# EnguinoShieldSchematic.net
KiCad netlist of a schematic drawn in EAGLE
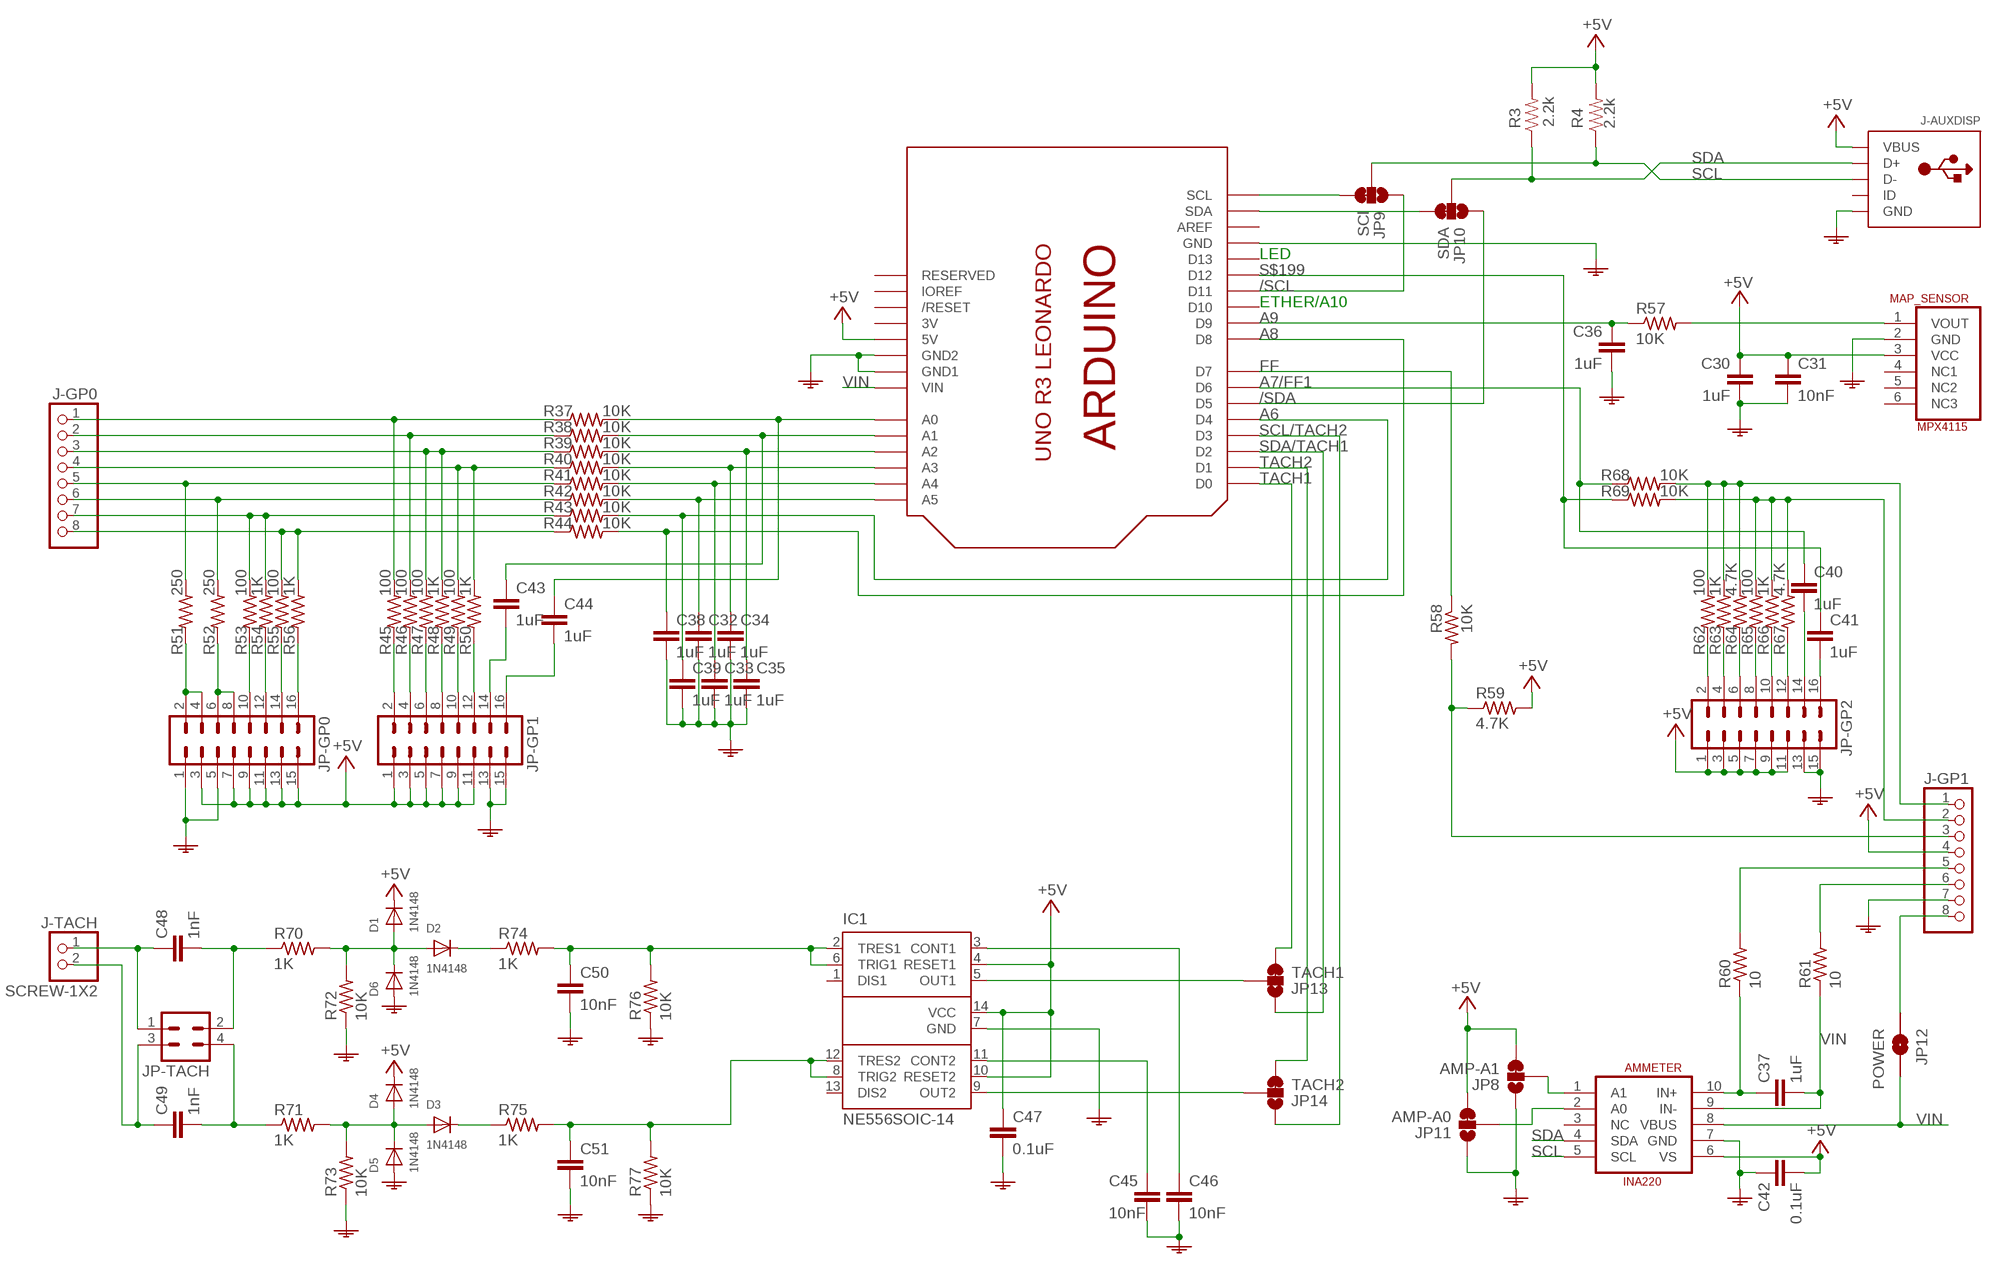
[diagram p0: schematic, sheet 1]
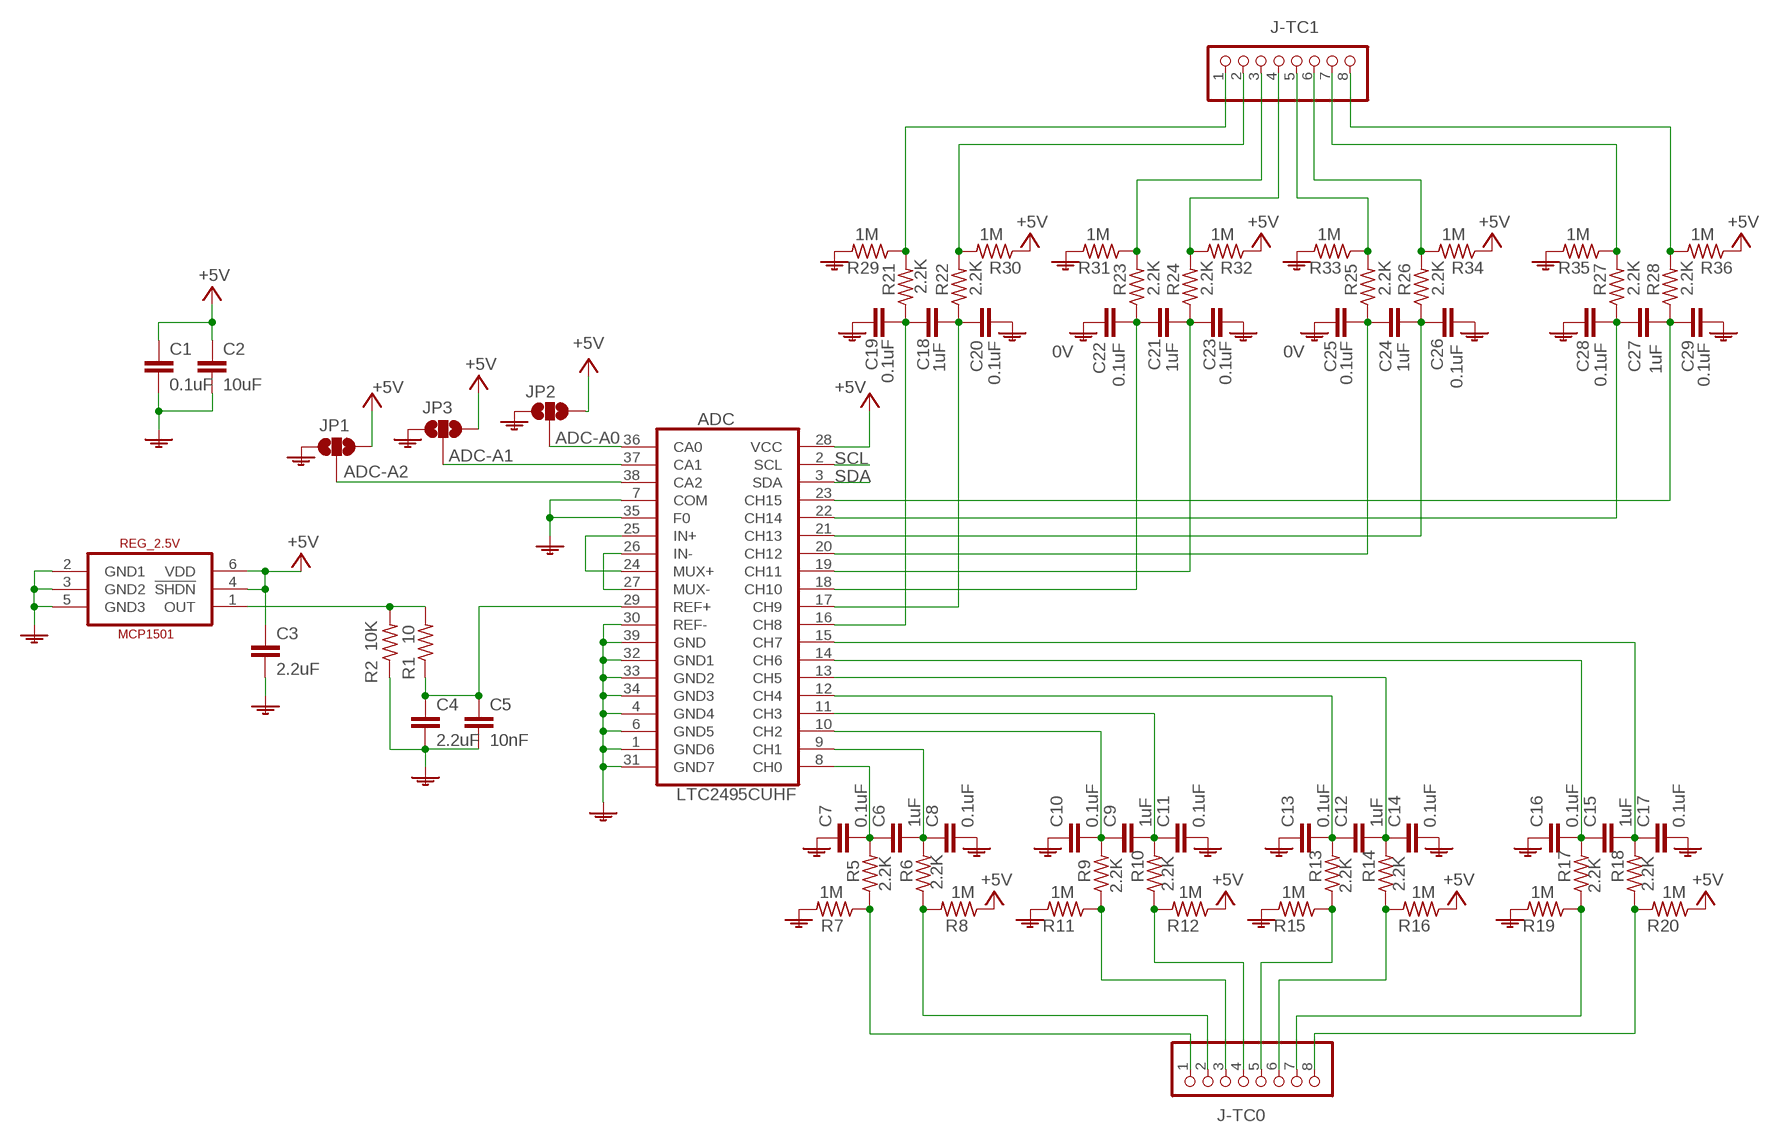
[diagram p1: schematic, sheet 2]

(export (version "E")
  (design (tool "Eeschema 10.0.6"))
  (components
    (comp (ref "AMMETER")
      (value "INA220")
      (footprint "eagle-import:VSSOP-10")
      (libsource (lib "eagle-import") (part "INA220"))
    )
    (comp (ref "C30")
      (value "1uF")
      (footprint "eagle-import:0603")
      (libsource (lib "eagle-import") (part "CAP-1UF10V"))
    )
    (comp (ref "C31")
      (value "10nF")
      (footprint "eagle-import:0603")
      (libsource (lib "eagle-import") (part "CAP-10NF"))
    )
    (comp (ref "C32")
      (value "1uF")
      (footprint "eagle-import:0603")
      (libsource (lib "eagle-import") (part "CAP-1UF10V"))
    )
    (comp (ref "C33")
      (value "1uF")
      (footprint "eagle-import:0603")
      (libsource (lib "eagle-import") (part "CAP-1UF10V"))
    )
    (comp (ref "C34")
      (value "1uF")
      (footprint "eagle-import:0603")
      (libsource (lib "eagle-import") (part "CAP-1UF10V"))
    )
    (comp (ref "C35")
      (value "1uF")
      (footprint "eagle-import:0603")
      (libsource (lib "eagle-import") (part "CAP-1UF10V"))
    )
    (comp (ref "C36")
      (value "1uF")
      (footprint "eagle-import:0603")
      (libsource (lib "eagle-import") (part "CAP-1UF10V"))
    )
    (comp (ref "C37")
      (value "1uF")
      (footprint "eagle-import:0603")
      (libsource (lib "eagle-import") (part "CAP-1UF10V"))
    )
    (comp (ref "C38")
      (value "1uF")
      (footprint "eagle-import:0603")
      (libsource (lib "eagle-import") (part "CAP-1UF10V"))
    )
    (comp (ref "C39")
      (value "1uF")
      (footprint "eagle-import:0603")
      (libsource (lib "eagle-import") (part "CAP-1UF10V"))
    )
    (comp (ref "C40")
      (value "1uF")
      (footprint "eagle-import:0603")
      (libsource (lib "eagle-import") (part "CAP-1UF10V"))
    )
    (comp (ref "C41")
      (value "1uF")
      (footprint "eagle-import:0603")
      (libsource (lib "eagle-import") (part "CAP-1UF10V"))
    )
    (comp (ref "C42")
      (value "0.1uF")
      (footprint "eagle-import:0603")
      (libsource (lib "eagle-import") (part "CAP-0.1UF10V"))
    )
    (comp (ref "C43")
      (value "1uF")
      (footprint "eagle-import:0603")
      (libsource (lib "eagle-import") (part "CAP-1UF10V"))
    )
    (comp (ref "C44")
      (value "1uF")
      (footprint "eagle-import:0603")
      (libsource (lib "eagle-import") (part "CAP-1UF10V"))
    )
    (comp (ref "C45")
      (value "10nF")
      (footprint "eagle-import:0603")
      (libsource (lib "eagle-import") (part "CAP-10NF"))
    )
    (comp (ref "C46")
      (value "10nF")
      (footprint "eagle-import:0603")
      (libsource (lib "eagle-import") (part "CAP-10NF"))
    )
    (comp (ref "C47")
      (value "0.1uF")
      (footprint "eagle-import:0603")
      (libsource (lib "eagle-import") (part "CAP-0.1UF10V"))
    )
    (comp (ref "C48")
      (value "1nF")
      (footprint "eagle-import:0603")
      (libsource (lib "eagle-import") (part "CAP-1NF"))
    )
    (comp (ref "C49")
      (value "1nF")
      (footprint "eagle-import:0603")
      (libsource (lib "eagle-import") (part "CAP-1NF"))
    )
    (comp (ref "C50")
      (value "10nF")
      (footprint "eagle-import:0603")
      (libsource (lib "eagle-import") (part "CAP-10NF"))
    )
    (comp (ref "C51")
      (value "10nF")
      (footprint "eagle-import:0603")
      (libsource (lib "eagle-import") (part "CAP-10NF"))
    )
    (comp (ref "D1")
      (value "1N4148")
      (footprint "eagle-import:SOD-123")
      (libsource (lib "eagle-import") (part "DIODESOD-123"))
    )
    (comp (ref "D2")
      (value "1N4148")
      (footprint "eagle-import:SOD-123")
      (libsource (lib "eagle-import") (part "DIODESOD-123"))
    )
    (comp (ref "D3")
      (value "1N4148")
      (footprint "eagle-import:SOD-123")
      (libsource (lib "eagle-import") (part "DIODESOD-123"))
    )
    (comp (ref "D4")
      (value "1N4148")
      (footprint "eagle-import:SOD-123")
      (libsource (lib "eagle-import") (part "DIODESOD-123"))
    )
    (comp (ref "D5")
      (value "1N4148")
      (footprint "eagle-import:SOD-123")
      (libsource (lib "eagle-import") (part "DIODESOD-123"))
    )
    (comp (ref "D6")
      (value "1N4148")
      (footprint "eagle-import:SOD-123")
      (libsource (lib "eagle-import") (part "DIODESOD-123"))
    )
    (comp (ref "IC1")
      (value "NE556SOIC-14")
      (footprint "eagle-import:SO14")
      (libsource (lib "eagle-import") (part "NE556SOIC-14"))
    )
    (comp (ref "J-AUXDISP")
      (value "USB-B-MICRO")
      (footprint "eagle-import:MICRO-USB-AMPHERNOL")
      (libsource (lib "eagle-import") (part "USB-B-MICRO"))
    )
    (comp (ref "J-GP0")
      (value "SCREW-1X8BIG")
      (footprint "eagle-import:1X08-BIG")
      (libsource (lib "eagle-import") (part "SCREW-1X8BIG"))
    )
    (comp (ref "J-GP1")
      (value "SCREW-1X8BIG")
      (footprint "eagle-import:1X08-BIG")
      (libsource (lib "eagle-import") (part "SCREW-1X8BIG"))
    )
    (comp (ref "J-TACH")
      (value "SCREW-1X2")
      (footprint "eagle-import:1X02-BIG")
      (libsource (lib "eagle-import") (part "SCREW-1X2"))
    )
    (comp (ref "JP-GP0")
      (value "MA08-2")
      (footprint "eagle-import:MA08-2")
      (libsource (lib "eagle-import") (part "MA08-2"))
    )
    (comp (ref "JP-GP1")
      (value "MA08-2")
      (footprint "eagle-import:MA08-2")
      (libsource (lib "eagle-import") (part "MA08-2"))
    )
    (comp (ref "JP-GP2")
      (value "MA08-2")
      (footprint "eagle-import:MA08-2")
      (libsource (lib "eagle-import") (part "MA08-2"))
    )
    (comp (ref "JP-TACH")
      (value "MA02-2")
      (footprint "eagle-import:MA02-2")
      (libsource (lib "eagle-import") (part "MA02-2"))
    )
    (comp (ref "JP8")
      (value "AMP-A1")
      (footprint "eagle-import:SMT-JUMPER_3_NC")
      (libsource (lib "eagle-import") (part "JUMPER-SMT_3-NC_NO-SILK"))
    )
    (comp (ref "JP9")
      (value "SCl")
      (footprint "eagle-import:SMT-JUMPER_3_NC")
      (libsource (lib "eagle-import") (part "JUMPER-SMT_3-NC_NO-SILK"))
    )
    (comp (ref "JP10")
      (value "SDA")
      (footprint "eagle-import:SMT-JUMPER_3_NC")
      (libsource (lib "eagle-import") (part "JUMPER-SMT_3-NC_NO-SILK"))
    )
    (comp (ref "JP11")
      (value "AMP-A0")
      (footprint "eagle-import:SMT-JUMPER_3_NC")
      (libsource (lib "eagle-import") (part "JUMPER-SMT_3-NC_NO-SILK"))
    )
    (comp (ref "JP12")
      (value "POWER")
      (footprint "eagle-import:SMT-JUMPER_2_NO")
      (libsource (lib "eagle-import") (part "JUMPER-SMT_2_NO_SILK"))
    )
    (comp (ref "JP13")
      (value "TACH1")
      (footprint "eagle-import:SMT-JUMPER_3_NC")
      (libsource (lib "eagle-import") (part "JUMPER-SMT_3-NC_NO-SILK"))
    )
    (comp (ref "JP14")
      (value "TACH2")
      (footprint "eagle-import:SMT-JUMPER_3_NC")
      (libsource (lib "eagle-import") (part "JUMPER-SMT_3-NC_NO-SILK"))
    )
    (comp (ref "MAP_SENSOR")
      (value "MPX4115")
      (footprint "eagle-import:MPX4115-AP")
      (libsource (lib "eagle-import") (part "MPX4115"))
    )
    (comp (ref "R3")
      (value "2.2k")
      (footprint "eagle-import:0603")
      (libsource (lib "eagle-import") (part "2.2KOHM-0603-1/10W-1%"))
    )
    (comp (ref "R4")
      (value "2.2k")
      (footprint "eagle-import:0603")
      (libsource (lib "eagle-import") (part "2.2KOHM-0603-1/10W-1%"))
    )
    (comp (ref "R37")
      (value "10K")
      (footprint "eagle-import:R0603")
      (libsource (lib "eagle-import") (part "R-US_R0603"))
    )
    (comp (ref "R38")
      (value "10K")
      (footprint "eagle-import:R0603")
      (libsource (lib "eagle-import") (part "R-US_R0603"))
    )
    (comp (ref "R39")
      (value "10K")
      (footprint "eagle-import:R0603")
      (libsource (lib "eagle-import") (part "R-US_R0603"))
    )
    (comp (ref "R40")
      (value "10K")
      (footprint "eagle-import:R0603")
      (libsource (lib "eagle-import") (part "R-US_R0603"))
    )
    (comp (ref "R41")
      (value "10K")
      (footprint "eagle-import:R0603")
      (libsource (lib "eagle-import") (part "R-US_R0603"))
    )
    (comp (ref "R42")
      (value "10K")
      (footprint "eagle-import:R0603")
      (libsource (lib "eagle-import") (part "R-US_R0603"))
    )
    (comp (ref "R43")
      (value "10K")
      (footprint "eagle-import:R0603")
      (libsource (lib "eagle-import") (part "R-US_R0603"))
    )
    (comp (ref "R44")
      (value "10K")
      (footprint "eagle-import:R0603")
      (libsource (lib "eagle-import") (part "R-US_R0603"))
    )
    (comp (ref "R45")
      (value "100")
      (footprint "eagle-import:R0603")
      (libsource (lib "eagle-import") (part "R-US_R0603"))
    )
    (comp (ref "R46")
      (value "100")
      (footprint "eagle-import:R0603")
      (libsource (lib "eagle-import") (part "R-US_R0603"))
    )
    (comp (ref "R47")
      (value "100")
      (footprint "eagle-import:R0603")
      (libsource (lib "eagle-import") (part "R-US_R0603"))
    )
    (comp (ref "R48")
      (value "1K")
      (footprint "eagle-import:R0603")
      (libsource (lib "eagle-import") (part "R-US_R0603"))
    )
    (comp (ref "R49")
      (value "100")
      (footprint "eagle-import:R0603")
      (libsource (lib "eagle-import") (part "R-US_R0603"))
    )
    (comp (ref "R50")
      (value "1K")
      (footprint "eagle-import:R0603")
      (libsource (lib "eagle-import") (part "R-US_R0603"))
    )
    (comp (ref "R51")
      (value "250")
      (footprint "eagle-import:R0603")
      (libsource (lib "eagle-import") (part "R-US_R0603"))
    )
    (comp (ref "R52")
      (value "250")
      (footprint "eagle-import:R0603")
      (libsource (lib "eagle-import") (part "R-US_R0603"))
    )
    (comp (ref "R53")
      (value "100")
      (footprint "eagle-import:R0603")
      (libsource (lib "eagle-import") (part "R-US_R0603"))
    )
    (comp (ref "R54")
      (value "1K")
      (footprint "eagle-import:R0603")
      (libsource (lib "eagle-import") (part "R-US_R0603"))
    )
    (comp (ref "R55")
      (value "100")
      (footprint "eagle-import:R0603")
      (libsource (lib "eagle-import") (part "R-US_R0603"))
    )
    (comp (ref "R56")
      (value "1K")
      (footprint "eagle-import:R0603")
      (libsource (lib "eagle-import") (part "R-US_R0603"))
    )
    (comp (ref "R57")
      (value "10K")
      (footprint "eagle-import:R0603")
      (libsource (lib "eagle-import") (part "R-US_R0603"))
    )
    (comp (ref "R58")
      (value "10K")
      (footprint "eagle-import:R0603")
      (libsource (lib "eagle-import") (part "R-US_R0603"))
    )
    (comp (ref "R59")
      (value "4.7K")
      (footprint "eagle-import:R0603")
      (libsource (lib "eagle-import") (part "R-US_R0603"))
    )
    (comp (ref "R60")
      (value "10")
      (footprint "eagle-import:R0603")
      (libsource (lib "eagle-import") (part "R-US_R0603"))
    )
    (comp (ref "R61")
      (value "10")
      (footprint "eagle-import:R0603")
      (libsource (lib "eagle-import") (part "R-US_R0603"))
    )
    (comp (ref "R62")
      (value "100")
      (footprint "eagle-import:R0603")
      (libsource (lib "eagle-import") (part "R-US_R0603"))
    )
    (comp (ref "R63")
      (value "1K")
      (footprint "eagle-import:R0603")
      (libsource (lib "eagle-import") (part "R-US_R0603"))
    )
    (comp (ref "R64")
      (value "4.7K")
      (footprint "eagle-import:R0603")
      (libsource (lib "eagle-import") (part "R-US_R0603"))
    )
    (comp (ref "R65")
      (value "100")
      (footprint "eagle-import:R0603")
      (libsource (lib "eagle-import") (part "R-US_R0603"))
    )
    (comp (ref "R66")
      (value "1K")
      (footprint "eagle-import:R0603")
      (libsource (lib "eagle-import") (part "R-US_R0603"))
    )
    (comp (ref "R67")
      (value "4.7K")
      (footprint "eagle-import:R0603")
      (libsource (lib "eagle-import") (part "R-US_R0603"))
    )
    (comp (ref "R68")
      (value "10K")
      (footprint "eagle-import:R0603")
      (libsource (lib "eagle-import") (part "R-US_R0603"))
    )
    (comp (ref "R69")
      (value "10K")
      (footprint "eagle-import:R0603")
      (libsource (lib "eagle-import") (part "R-US_R0603"))
    )
    (comp (ref "R70")
      (value "1K")
      (footprint "eagle-import:R0603")
      (libsource (lib "eagle-import") (part "R-US_R0603"))
    )
    (comp (ref "R71")
      (value "1K")
      (footprint "eagle-import:R0603")
      (libsource (lib "eagle-import") (part "R-US_R0603"))
    )
    (comp (ref "R72")
      (value "10K")
      (footprint "eagle-import:R0603")
      (libsource (lib "eagle-import") (part "R-US_R0603"))
    )
    (comp (ref "R73")
      (value "10K")
      (footprint "eagle-import:R0603")
      (libsource (lib "eagle-import") (part "R-US_R0603"))
    )
    (comp (ref "R74")
      (value "1K")
      (footprint "eagle-import:R0603")
      (libsource (lib "eagle-import") (part "R-US_R0603"))
    )
    (comp (ref "R75")
      (value "1K")
      (footprint "eagle-import:R0603")
      (libsource (lib "eagle-import") (part "R-US_R0603"))
    )
    (comp (ref "R76")
      (value "10K")
      (footprint "eagle-import:R0603")
      (libsource (lib "eagle-import") (part "R-US_R0603"))
    )
    (comp (ref "R77")
      (value "10K")
      (footprint "eagle-import:R0603")
      (libsource (lib "eagle-import") (part "R-US_R0603"))
    )
    (comp (ref "U1")
      (value "ARDUINOR3LEO-DIMENSION")
      (footprint "eagle-import:ARDUINOR3")
      (libsource (lib "eagle-import") (part "ARDUINOR3LEO-DIMENSION"))
    )
    (comp (ref "ADC")
      (value "LTC2495CUHF")
      (footprint "eagle-import:QFN-38")
      (libsource (lib "eagle-import") (part "LTC2495CUHF"))
    )
    (comp (ref "C1")
      (value "0.1uF")
      (footprint "eagle-import:0603")
      (libsource (lib "eagle-import") (part "CAP-0.1UF10V"))
    )
    (comp (ref "C2")
      (value "10uF")
      (footprint "eagle-import:0603")
      (libsource (lib "eagle-import") (part "CAP-10UF10V"))
    )
    (comp (ref "C3")
      (value "2.2uF")
      (footprint "eagle-import:0603")
      (libsource (lib "eagle-import") (part "CAP-2.2UF10V"))
    )
    (comp (ref "C4")
      (value "2.2uF")
      (footprint "eagle-import:0603")
      (libsource (lib "eagle-import") (part "CAP-2.2UF10V"))
    )
    (comp (ref "C5")
      (value "10nF")
      (footprint "eagle-import:0603")
      (libsource (lib "eagle-import") (part "CAP-10NF"))
    )
    (comp (ref "C6")
      (value "1uF")
      (footprint "eagle-import:0603")
      (libsource (lib "eagle-import") (part "CAP-1UF10V"))
    )
    (comp (ref "C7")
      (value "0.1uF")
      (footprint "eagle-import:0603")
      (libsource (lib "eagle-import") (part "CAP-0.1UF10V"))
    )
    (comp (ref "C8")
      (value "0.1uF")
      (footprint "eagle-import:0603")
      (libsource (lib "eagle-import") (part "CAP-0.1UF10V"))
    )
    (comp (ref "C9")
      (value "1uF")
      (footprint "eagle-import:0603")
      (libsource (lib "eagle-import") (part "CAP-1UF10V"))
    )
    (comp (ref "C10")
      (value "0.1uF")
      (footprint "eagle-import:0603")
      (libsource (lib "eagle-import") (part "CAP-0.1UF10V"))
    )
    (comp (ref "C11")
      (value "0.1uF")
      (footprint "eagle-import:0603")
      (libsource (lib "eagle-import") (part "CAP-0.1UF10V"))
    )
    (comp (ref "C12")
      (value "1uF")
      (footprint "eagle-import:0603")
      (libsource (lib "eagle-import") (part "CAP-1UF10V"))
    )
    (comp (ref "C13")
      (value "0.1uF")
      (footprint "eagle-import:0603")
      (libsource (lib "eagle-import") (part "CAP-0.1UF10V"))
    )
    (comp (ref "C14")
      (value "0.1uF")
      (footprint "eagle-import:0603")
      (libsource (lib "eagle-import") (part "CAP-0.1UF10V"))
    )
    (comp (ref "C15")
      (value "1uF")
      (footprint "eagle-import:0603")
      (libsource (lib "eagle-import") (part "CAP-1UF10V"))
    )
    (comp (ref "C16")
      (value "0.1uF")
      (footprint "eagle-import:0603")
      (libsource (lib "eagle-import") (part "CAP-0.1UF10V"))
    )
    (comp (ref "C17")
      (value "0.1uF")
      (footprint "eagle-import:0603")
      (libsource (lib "eagle-import") (part "CAP-0.1UF10V"))
    )
    (comp (ref "C18")
      (value "1uF")
      (footprint "eagle-import:0603")
      (libsource (lib "eagle-import") (part "CAP-1UF10V"))
    )
    (comp (ref "C19")
      (value "0.1uF")
      (footprint "eagle-import:0603")
      (libsource (lib "eagle-import") (part "CAP-0.1UF10V"))
    )
    (comp (ref "C20")
      (value "0.1uF")
      (footprint "eagle-import:0603")
      (libsource (lib "eagle-import") (part "CAP-0.1UF10V"))
    )
    (comp (ref "C21")
      (value "1uF")
      (footprint "eagle-import:0603")
      (libsource (lib "eagle-import") (part "CAP-1UF10V"))
    )
    (comp (ref "C22")
      (value "0.1uF")
      (footprint "eagle-import:0603")
      (libsource (lib "eagle-import") (part "CAP-0.1UF10V"))
    )
    (comp (ref "C23")
      (value "0.1uF")
      (footprint "eagle-import:0603")
      (libsource (lib "eagle-import") (part "CAP-0.1UF10V"))
    )
    (comp (ref "C24")
      (value "1uF")
      (footprint "eagle-import:0603")
      (libsource (lib "eagle-import") (part "CAP-1UF10V"))
    )
    (comp (ref "C25")
      (value "0.1uF")
      (footprint "eagle-import:0603")
      (libsource (lib "eagle-import") (part "CAP-0.1UF10V"))
    )
    (comp (ref "C26")
      (value "0.1uF")
      (footprint "eagle-import:0603")
      (libsource (lib "eagle-import") (part "CAP-0.1UF10V"))
    )
    (comp (ref "C27")
      (value "1uF")
      (footprint "eagle-import:0603")
      (libsource (lib "eagle-import") (part "CAP-1UF10V"))
    )
    (comp (ref "C28")
      (value "0.1uF")
      (footprint "eagle-import:0603")
      (libsource (lib "eagle-import") (part "CAP-0.1UF10V"))
    )
    (comp (ref "C29")
      (value "0.1uF")
      (footprint "eagle-import:0603")
      (libsource (lib "eagle-import") (part "CAP-0.1UF10V"))
    )
    (comp (ref "J-TC0")
      (value "SCREW-1X8BIG")
      (footprint "eagle-import:1X08-BIG")
      (libsource (lib "eagle-import") (part "SCREW-1X8BIG"))
    )
    (comp (ref "J-TC1")
      (value "SCREW-1X8BIG")
      (footprint "eagle-import:1X08-BIG")
      (libsource (lib "eagle-import") (part "SCREW-1X8BIG"))
    )
    (comp (ref "JP1")
      (value "ADC-A2")
      (footprint "eagle-import:SMT-JUMPER_3_NO")
      (libsource (lib "eagle-import") (part "JUMPER-SMT_3_NO_NO-SILK"))
    )
    (comp (ref "JP2")
      (value "ADC-A0")
      (footprint "eagle-import:SMT-JUMPER_3_NO")
      (libsource (lib "eagle-import") (part "JUMPER-SMT_3_NO_NO-SILK"))
    )
    (comp (ref "JP3")
      (value "ADC-A1")
      (footprint "eagle-import:SMT-JUMPER_3_NO")
      (libsource (lib "eagle-import") (part "JUMPER-SMT_3_NO_NO-SILK"))
    )
    (comp (ref "R1")
      (value "10")
      (footprint "eagle-import:R0603")
      (libsource (lib "eagle-import") (part "R-US_R0603"))
    )
    (comp (ref "R2")
      (value "10K")
      (footprint "eagle-import:R0603")
      (libsource (lib "eagle-import") (part "R-US_R0603"))
    )
    (comp (ref "R5")
      (value "2.2K")
      (footprint "eagle-import:R0603")
      (libsource (lib "eagle-import") (part "R-US_R0603"))
    )
    (comp (ref "R6")
      (value "2.2K")
      (footprint "eagle-import:R0603")
      (libsource (lib "eagle-import") (part "R-US_R0603"))
    )
    (comp (ref "R7")
      (value "1M")
      (footprint "eagle-import:R0603")
      (libsource (lib "eagle-import") (part "R-US_R0603"))
    )
    (comp (ref "R8")
      (value "1M")
      (footprint "eagle-import:R0603")
      (libsource (lib "eagle-import") (part "R-US_R0603"))
    )
    (comp (ref "R9")
      (value "2.2K")
      (footprint "eagle-import:R0603")
      (libsource (lib "eagle-import") (part "R-US_R0603"))
    )
    (comp (ref "R10")
      (value "2.2K")
      (footprint "eagle-import:R0603")
      (libsource (lib "eagle-import") (part "R-US_R0603"))
    )
    (comp (ref "R11")
      (value "1M")
      (footprint "eagle-import:R0603")
      (libsource (lib "eagle-import") (part "R-US_R0603"))
    )
    (comp (ref "R12")
      (value "1M")
      (footprint "eagle-import:R0603")
      (libsource (lib "eagle-import") (part "R-US_R0603"))
    )
    (comp (ref "R13")
      (value "2.2K")
      (footprint "eagle-import:R0603")
      (libsource (lib "eagle-import") (part "R-US_R0603"))
    )
    (comp (ref "R14")
      (value "2.2K")
      (footprint "eagle-import:R0603")
      (libsource (lib "eagle-import") (part "R-US_R0603"))
    )
    (comp (ref "R15")
      (value "1M")
      (footprint "eagle-import:R0603")
      (libsource (lib "eagle-import") (part "R-US_R0603"))
    )
    (comp (ref "R16")
      (value "1M")
      (footprint "eagle-import:R0603")
      (libsource (lib "eagle-import") (part "R-US_R0603"))
    )
    (comp (ref "R17")
      (value "2.2K")
      (footprint "eagle-import:R0603")
      (libsource (lib "eagle-import") (part "R-US_R0603"))
    )
    (comp (ref "R18")
      (value "2.2K")
      (footprint "eagle-import:R0603")
      (libsource (lib "eagle-import") (part "R-US_R0603"))
    )
    (comp (ref "R19")
      (value "1M")
      (footprint "eagle-import:R0603")
      (libsource (lib "eagle-import") (part "R-US_R0603"))
    )
    (comp (ref "R20")
      (value "1M")
      (footprint "eagle-import:R0603")
      (libsource (lib "eagle-import") (part "R-US_R0603"))
    )
    (comp (ref "R21")
      (value "2.2K")
      (footprint "eagle-import:R0603")
      (libsource (lib "eagle-import") (part "R-US_R0603"))
    )
    (comp (ref "R22")
      (value "2.2K")
      (footprint "eagle-import:R0603")
      (libsource (lib "eagle-import") (part "R-US_R0603"))
    )
    (comp (ref "R23")
      (value "2.2K")
      (footprint "eagle-import:R0603")
      (libsource (lib "eagle-import") (part "R-US_R0603"))
    )
    (comp (ref "R24")
      (value "2.2K")
      (footprint "eagle-import:R0603")
      (libsource (lib "eagle-import") (part "R-US_R0603"))
    )
    (comp (ref "R25")
      (value "2.2K")
      (footprint "eagle-import:R0603")
      (libsource (lib "eagle-import") (part "R-US_R0603"))
    )
    (comp (ref "R26")
      (value "2.2K")
      (footprint "eagle-import:R0603")
      (libsource (lib "eagle-import") (part "R-US_R0603"))
    )
    (comp (ref "R27")
      (value "2.2K")
      (footprint "eagle-import:R0603")
      (libsource (lib "eagle-import") (part "R-US_R0603"))
    )
    (comp (ref "R28")
      (value "2.2K")
      (footprint "eagle-import:R0603")
      (libsource (lib "eagle-import") (part "R-US_R0603"))
    )
    (comp (ref "R29")
      (value "1M")
      (footprint "eagle-import:R0603")
      (libsource (lib "eagle-import") (part "R-US_R0603"))
    )
    (comp (ref "R30")
      (value "1M")
      (footprint "eagle-import:R0603")
      (libsource (lib "eagle-import") (part "R-US_R0603"))
    )
    (comp (ref "R31")
      (value "1M")
      (footprint "eagle-import:R0603")
      (libsource (lib "eagle-import") (part "R-US_R0603"))
    )
    (comp (ref "R32")
      (value "1M")
      (footprint "eagle-import:R0603")
      (libsource (lib "eagle-import") (part "R-US_R0603"))
    )
    (comp (ref "R33")
      (value "1M")
      (footprint "eagle-import:R0603")
      (libsource (lib "eagle-import") (part "R-US_R0603"))
    )
    (comp (ref "R34")
      (value "1M")
      (footprint "eagle-import:R0603")
      (libsource (lib "eagle-import") (part "R-US_R0603"))
    )
    (comp (ref "R35")
      (value "1M")
      (footprint "eagle-import:R0603")
      (libsource (lib "eagle-import") (part "R-US_R0603"))
    )
    (comp (ref "R36")
      (value "1M")
      (footprint "eagle-import:R0603")
      (libsource (lib "eagle-import") (part "R-US_R0603"))
    )
    (comp (ref "REG_2.5V")
      (value "MCP1501")
      (footprint "eagle-import:SOT23-6")
      (libsource (lib "eagle-import") (part "MCP1501"))
    )
  )
  (nets
    (net (code "1") (name "+5V") (class "Default")
      (node (ref "ADC") (pin "28") (pinfunction "VCC_28") (pintype "power_in"))
      (node (ref "AMMETER") (pin "6") (pinfunction "VS_6") (pintype "power_in"))
      (node (ref "C1") (pin "1") (pinfunction "1_1") (pintype "passive"))
      (node (ref "C2") (pin "1") (pinfunction "1_1") (pintype "passive"))
      (node (ref "C3") (pin "1") (pinfunction "1_1") (pintype "passive"))
      (node (ref "C30") (pin "1") (pinfunction "1_1") (pintype "passive"))
      (node (ref "C31") (pin "1") (pinfunction "1_1") (pintype "passive"))
      (node (ref "C42") (pin "2") (pinfunction "2_2") (pintype "passive"))
      (node (ref "C47") (pin "1") (pinfunction "1_1") (pintype "passive"))
      (node (ref "D1") (pin "C") (pinfunction "C_C") (pintype "passive"))
      (node (ref "D4") (pin "C") (pinfunction "C_C") (pintype "passive"))
      (node (ref "IC1") (pin "10") (pinfunction "RESET2_10") (pintype "input"))
      (node (ref "IC1") (pin "14") (pinfunction "VCC_14") (pintype "power_in"))
      (node (ref "IC1") (pin "4") (pinfunction "RESET1_4") (pintype "input"))
      (node (ref "J-AUXDISP") (pin "P$1") (pinfunction "VBUS_P$1") (pintype "power_in"))
      (node (ref "J-GP1") (pin "4") (pinfunction "4_4") (pintype "passive"))
      (node (ref "JP-GP0") (pin "11") (pinfunction "11_11") (pintype "passive"))
      (node (ref "JP-GP0") (pin "13") (pinfunction "13_13") (pintype "passive"))
      (node (ref "JP-GP0") (pin "15") (pinfunction "15_15") (pintype "passive"))
      (node (ref "JP-GP0") (pin "3") (pinfunction "3_3") (pintype "passive"))
      (node (ref "JP-GP0") (pin "7") (pinfunction "7_7") (pintype "passive"))
      (node (ref "JP-GP0") (pin "9") (pinfunction "9_9") (pintype "passive"))
      (node (ref "JP-GP1") (pin "1") (pinfunction "1_1") (pintype "passive"))
      (node (ref "JP-GP1") (pin "11") (pinfunction "11_11") (pintype "passive"))
      (node (ref "JP-GP1") (pin "3") (pinfunction "3_3") (pintype "passive"))
      (node (ref "JP-GP1") (pin "5") (pinfunction "5_5") (pintype "passive"))
      (node (ref "JP-GP1") (pin "7") (pinfunction "7_7") (pintype "passive"))
      (node (ref "JP-GP1") (pin "9") (pinfunction "9_9") (pintype "passive"))
      (node (ref "JP-GP2") (pin "1") (pinfunction "1_1") (pintype "passive"))
      (node (ref "JP-GP2") (pin "11") (pinfunction "11_11") (pintype "passive"))
      (node (ref "JP-GP2") (pin "3") (pinfunction "3_3") (pintype "passive"))
      (node (ref "JP-GP2") (pin "5") (pinfunction "5_5") (pintype "passive"))
      (node (ref "JP-GP2") (pin "7") (pinfunction "7_7") (pintype "passive"))
      (node (ref "JP-GP2") (pin "9") (pinfunction "9_9") (pintype "passive"))
      (node (ref "JP1") (pin "3") (pinfunction "3_3") (pintype "passive"))
      (node (ref "JP11") (pin "3") (pinfunction "3_3") (pintype "passive"))
      (node (ref "JP2") (pin "3") (pinfunction "3_3") (pintype "passive"))
      (node (ref "JP3") (pin "3") (pinfunction "3_3") (pintype "passive"))
      (node (ref "JP8") (pin "3") (pinfunction "3_3") (pintype "passive"))
      (node (ref "MAP_SENSOR") (pin "3") (pinfunction "VCC_3") (pintype "power_in"))
      (node (ref "R12") (pin "1") (pinfunction "1_1") (pintype "passive"))
      (node (ref "R16") (pin "1") (pinfunction "1_1") (pintype "passive"))
      (node (ref "R20") (pin "1") (pinfunction "1_1") (pintype "passive"))
      (node (ref "R3") (pin "2") (pinfunction "2_2") (pintype "passive"))
      (node (ref "R30") (pin "1") (pinfunction "1_1") (pintype "passive"))
      (node (ref "R32") (pin "1") (pinfunction "1_1") (pintype "passive"))
      (node (ref "R34") (pin "1") (pinfunction "1_1") (pintype "passive"))
      (node (ref "R36") (pin "1") (pinfunction "1_1") (pintype "passive"))
      (node (ref "R4") (pin "2") (pinfunction "2_2") (pintype "passive"))
      (node (ref "R59") (pin "2") (pinfunction "2_2") (pintype "passive"))
      (node (ref "R8") (pin "1") (pinfunction "1_1") (pintype "passive"))
      (node (ref "REG_2.5V") (pin "4") (pinfunction "~{SHDN}_4") (pintype "bidirectional"))
      (node (ref "REG_2.5V") (pin "6") (pinfunction "VDD_6") (pintype "power_in"))
      (node (ref "U1") (pin "5V") (pinfunction "5V_5V") (pintype "power_in"))
    )
    (net (code "2") (name "0V") (class "Default")
      (node (ref "ADC") (pin "1") (pinfunction "GND6_1") (pintype "power_in"))
      (node (ref "ADC") (pin "30") (pinfunction "REF-_30") (pintype "bidirectional"))
      (node (ref "ADC") (pin "31") (pinfunction "GND7_31") (pintype "power_in"))
      (node (ref "ADC") (pin "32") (pinfunction "GND1_32") (pintype "power_in"))
      (node (ref "ADC") (pin "33") (pinfunction "GND2_33") (pintype "power_in"))
      (node (ref "ADC") (pin "34") (pinfunction "GND3_34") (pintype "power_in"))
      (node (ref "ADC") (pin "35") (pinfunction "F0_35") (pintype "bidirectional"))
      (node (ref "ADC") (pin "39") (pinfunction "GND_39") (pintype "power_in"))
      (node (ref "ADC") (pin "4") (pinfunction "GND4_4") (pintype "power_in"))
      (node (ref "ADC") (pin "6") (pinfunction "GND5_6") (pintype "power_in"))
      (node (ref "ADC") (pin "7") (pinfunction "COM_7") (pintype "bidirectional"))
      (node (ref "AMMETER") (pin "7") (pinfunction "GND_7") (pintype "power_in"))
      (node (ref "C1") (pin "2") (pinfunction "2_2") (pintype "passive"))
      (node (ref "C10") (pin "1") (pinfunction "1_1") (pintype "passive"))
      (node (ref "C11") (pin "2") (pinfunction "2_2") (pintype "passive"))
      (node (ref "C13") (pin "1") (pinfunction "1_1") (pintype "passive"))
      (node (ref "C14") (pin "2") (pinfunction "2_2") (pintype "passive"))
      (node (ref "C16") (pin "1") (pinfunction "1_1") (pintype "passive"))
      (node (ref "C17") (pin "2") (pinfunction "2_2") (pintype "passive"))
      (node (ref "C19") (pin "1") (pinfunction "1_1") (pintype "passive"))
      (node (ref "C2") (pin "2") (pinfunction "2_2") (pintype "passive"))
      (node (ref "C20") (pin "2") (pinfunction "2_2") (pintype "passive"))
      (node (ref "C22") (pin "1") (pinfunction "1_1") (pintype "passive"))
      (node (ref "C23") (pin "2") (pinfunction "2_2") (pintype "passive"))
      (node (ref "C25") (pin "1") (pinfunction "1_1") (pintype "passive"))
      (node (ref "C26") (pin "2") (pinfunction "2_2") (pintype "passive"))
      (node (ref "C28") (pin "1") (pinfunction "1_1") (pintype "passive"))
      (node (ref "C29") (pin "2") (pinfunction "2_2") (pintype "passive"))
      (node (ref "C3") (pin "2") (pinfunction "2_2") (pintype "passive"))
      (node (ref "C30") (pin "2") (pinfunction "2_2") (pintype "passive"))
      (node (ref "C31") (pin "2") (pinfunction "2_2") (pintype "passive"))
      (node (ref "C32") (pin "2") (pinfunction "2_2") (pintype "passive"))
      (node (ref "C33") (pin "2") (pinfunction "2_2") (pintype "passive"))
      (node (ref "C34") (pin "2") (pinfunction "2_2") (pintype "passive"))
      (node (ref "C35") (pin "2") (pinfunction "2_2") (pintype "passive"))
      (node (ref "C36") (pin "2") (pinfunction "2_2") (pintype "passive"))
      (node (ref "C38") (pin "2") (pinfunction "2_2") (pintype "passive"))
      (node (ref "C39") (pin "2") (pinfunction "2_2") (pintype "passive"))
      (node (ref "C4") (pin "2") (pinfunction "2_2") (pintype "passive"))
      (node (ref "C42") (pin "1") (pinfunction "1_1") (pintype "passive"))
      (node (ref "C45") (pin "2") (pinfunction "2_2") (pintype "passive"))
      (node (ref "C46") (pin "2") (pinfunction "2_2") (pintype "passive"))
      (node (ref "C47") (pin "2") (pinfunction "2_2") (pintype "passive"))
      (node (ref "C5") (pin "2") (pinfunction "2_2") (pintype "passive"))
      (node (ref "C50") (pin "2") (pinfunction "2_2") (pintype "passive"))
      (node (ref "C51") (pin "2") (pinfunction "2_2") (pintype "passive"))
      (node (ref "C7") (pin "1") (pinfunction "1_1") (pintype "passive"))
      (node (ref "C8") (pin "2") (pinfunction "2_2") (pintype "passive"))
      (node (ref "D5") (pin "A") (pinfunction "A_A") (pintype "passive"))
      (node (ref "D6") (pin "A") (pinfunction "A_A") (pintype "passive"))
      (node (ref "IC1") (pin "7") (pinfunction "GND_7") (pintype "power_in"))
      (node (ref "J-AUXDISP") (pin "P$5") (pinfunction "GND_P$5") (pintype "power_in"))
      (node (ref "J-GP1") (pin "7") (pinfunction "7_7") (pintype "passive"))
      (node (ref "JP-GP0") (pin "1") (pinfunction "1_1") (pintype "passive"))
      (node (ref "JP-GP0") (pin "5") (pinfunction "5_5") (pintype "passive"))
      (node (ref "JP-GP1") (pin "13") (pinfunction "13_13") (pintype "passive"))
      (node (ref "JP-GP1") (pin "15") (pinfunction "15_15") (pintype "passive"))
      (node (ref "JP-GP2") (pin "13") (pinfunction "13_13") (pintype "passive"))
      (node (ref "JP-GP2") (pin "15") (pinfunction "15_15") (pintype "passive"))
      (node (ref "JP1") (pin "1") (pinfunction "1_1") (pintype "passive"))
      (node (ref "JP11") (pin "1") (pinfunction "1_1") (pintype "passive"))
      (node (ref "JP2") (pin "1") (pinfunction "1_1") (pintype "passive"))
      (node (ref "JP3") (pin "1") (pinfunction "1_1") (pintype "passive"))
      (node (ref "JP8") (pin "1") (pinfunction "1_1") (pintype "passive"))
      (node (ref "MAP_SENSOR") (pin "2") (pinfunction "GND_2") (pintype "power_in"))
      (node (ref "R11") (pin "2") (pinfunction "2_2") (pintype "passive"))
      (node (ref "R15") (pin "2") (pinfunction "2_2") (pintype "passive"))
      (node (ref "R19") (pin "2") (pinfunction "2_2") (pintype "passive"))
      (node (ref "R2") (pin "1") (pinfunction "1_1") (pintype "passive"))
      (node (ref "R29") (pin "2") (pinfunction "2_2") (pintype "passive"))
      (node (ref "R31") (pin "2") (pinfunction "2_2") (pintype "passive"))
      (node (ref "R33") (pin "2") (pinfunction "2_2") (pintype "passive"))
      (node (ref "R35") (pin "2") (pinfunction "2_2") (pintype "passive"))
      (node (ref "R7") (pin "2") (pinfunction "2_2") (pintype "passive"))
      (node (ref "R72") (pin "1") (pinfunction "1_1") (pintype "passive"))
      (node (ref "R73") (pin "1") (pinfunction "1_1") (pintype "passive"))
      (node (ref "R76") (pin "1") (pinfunction "1_1") (pintype "passive"))
      (node (ref "R77") (pin "1") (pinfunction "1_1") (pintype "passive"))
      (node (ref "REG_2.5V") (pin "2") (pinfunction "GND1_2") (pintype "power_in"))
      (node (ref "REG_2.5V") (pin "3") (pinfunction "GND2_3") (pintype "power_in"))
      (node (ref "REG_2.5V") (pin "5") (pinfunction "GND3_5") (pintype "power_in"))
      (node (ref "U1") (pin "GND") (pinfunction "GND_GND") (pintype "power_in"))
      (node (ref "U1") (pin "GND1") (pinfunction "GND1_GND1") (pintype "power_in"))
      (node (ref "U1") (pin "GND2") (pinfunction "GND2_GND2") (pintype "power_in"))
    )
    (net (code "3") (name "3V") (class "Default")
      (node (ref "U1") (pin "3V") (pinfunction "3V_3V") (pintype "power_in"))
    )
    (net (code "4") (name "A6") (class "Default")
      (node (ref "C39") (pin "1") (pinfunction "1_1") (pintype "passive"))
      (node (ref "R43") (pin "2") (pinfunction "2_2") (pintype "passive"))
      (node (ref "U1") (pin "D4") (pinfunction "D4_D4") (pintype "bidirectional"))
    )
    (net (code "5") (name "A7{slash}FF1") (class "Default")
      (node (ref "C40") (pin "1") (pinfunction "1_1") (pintype "passive"))
      (node (ref "R68") (pin "1") (pinfunction "1_1") (pintype "passive"))
      (node (ref "U1") (pin "D6") (pinfunction "D6_D6") (pintype "bidirectional"))
    )
    (net (code "6") (name "A8") (class "Default")
      (node (ref "C38") (pin "1") (pinfunction "1_1") (pintype "passive"))
      (node (ref "R44") (pin "2") (pinfunction "2_2") (pintype "passive"))
      (node (ref "U1") (pin "D8") (pinfunction "D8_D8") (pintype "bidirectional"))
    )
    (net (code "7") (name "A9") (class "Default")
      (node (ref "C36") (pin "1") (pinfunction "1_1") (pintype "passive"))
      (node (ref "R57") (pin "1") (pinfunction "1_1") (pintype "passive"))
      (node (ref "U1") (pin "D9") (pinfunction "D9_D9") (pintype "bidirectional"))
    )
    (net (code "8") (name "FF") (class "Default")
      (node (ref "R58") (pin "1") (pinfunction "1_1") (pintype "passive"))
      (node (ref "U1") (pin "D7") (pinfunction "D7_D7") (pintype "bidirectional"))
    )
    (net (code "9") (name "Net-(ADC-CA0)") (class "Default")
      (node (ref "ADC") (pin "36") (pinfunction "CA0_36") (pintype "bidirectional"))
      (node (ref "JP2") (pin "2") (pinfunction "2_2") (pintype "passive"))
    )
    (net (code "10") (name "Net-(ADC-CA1)") (class "Default")
      (node (ref "ADC") (pin "37") (pinfunction "CA1_37") (pintype "bidirectional"))
      (node (ref "JP3") (pin "2") (pinfunction "2_2") (pintype "passive"))
    )
    (net (code "11") (name "Net-(ADC-CA2)") (class "Default")
      (node (ref "ADC") (pin "38") (pinfunction "CA2_38") (pintype "bidirectional"))
      (node (ref "JP1") (pin "2") (pinfunction "2_2") (pintype "passive"))
    )
    (net (code "12") (name "Net-(ADC-CH0)") (class "Default")
      (node (ref "ADC") (pin "8") (pinfunction "CH0_8") (pintype "bidirectional"))
      (node (ref "C6") (pin "1") (pinfunction "1_1") (pintype "passive"))
      (node (ref "C7") (pin "2") (pinfunction "2_2") (pintype "passive"))
      (node (ref "R5") (pin "2") (pinfunction "2_2") (pintype "passive"))
    )
    (net (code "13") (name "Net-(ADC-CH1)") (class "Default")
      (node (ref "ADC") (pin "9") (pinfunction "CH1_9") (pintype "bidirectional"))
      (node (ref "C6") (pin "2") (pinfunction "2_2") (pintype "passive"))
      (node (ref "C8") (pin "1") (pinfunction "1_1") (pintype "passive"))
      (node (ref "R6") (pin "2") (pinfunction "2_2") (pintype "passive"))
    )
    (net (code "14") (name "Net-(ADC-CH2)") (class "Default")
      (node (ref "ADC") (pin "10") (pinfunction "CH2_10") (pintype "bidirectional"))
      (node (ref "C10") (pin "2") (pinfunction "2_2") (pintype "passive"))
      (node (ref "C9") (pin "1") (pinfunction "1_1") (pintype "passive"))
      (node (ref "R9") (pin "2") (pinfunction "2_2") (pintype "passive"))
    )
    (net (code "15") (name "Net-(ADC-CH3)") (class "Default")
      (node (ref "ADC") (pin "11") (pinfunction "CH3_11") (pintype "bidirectional"))
      (node (ref "C11") (pin "1") (pinfunction "1_1") (pintype "passive"))
      (node (ref "C9") (pin "2") (pinfunction "2_2") (pintype "passive"))
      (node (ref "R10") (pin "2") (pinfunction "2_2") (pintype "passive"))
    )
    (net (code "16") (name "Net-(ADC-CH4)") (class "Default")
      (node (ref "ADC") (pin "12") (pinfunction "CH4_12") (pintype "bidirectional"))
      (node (ref "C12") (pin "1") (pinfunction "1_1") (pintype "passive"))
      (node (ref "C13") (pin "2") (pinfunction "2_2") (pintype "passive"))
      (node (ref "R13") (pin "2") (pinfunction "2_2") (pintype "passive"))
    )
    (net (code "17") (name "Net-(ADC-CH5)") (class "Default")
      (node (ref "ADC") (pin "13") (pinfunction "CH5_13") (pintype "bidirectional"))
      (node (ref "C12") (pin "2") (pinfunction "2_2") (pintype "passive"))
      (node (ref "C14") (pin "1") (pinfunction "1_1") (pintype "passive"))
      (node (ref "R14") (pin "2") (pinfunction "2_2") (pintype "passive"))
    )
    (net (code "18") (name "Net-(ADC-CH6)") (class "Default")
      (node (ref "ADC") (pin "14") (pinfunction "CH6_14") (pintype "bidirectional"))
      (node (ref "C15") (pin "1") (pinfunction "1_1") (pintype "passive"))
      (node (ref "C16") (pin "2") (pinfunction "2_2") (pintype "passive"))
      (node (ref "R17") (pin "2") (pinfunction "2_2") (pintype "passive"))
    )
    (net (code "19") (name "Net-(ADC-CH7)") (class "Default")
      (node (ref "ADC") (pin "15") (pinfunction "CH7_15") (pintype "bidirectional"))
      (node (ref "C15") (pin "2") (pinfunction "2_2") (pintype "passive"))
      (node (ref "C17") (pin "1") (pinfunction "1_1") (pintype "passive"))
      (node (ref "R18") (pin "2") (pinfunction "2_2") (pintype "passive"))
    )
    (net (code "20") (name "Net-(ADC-CH8)") (class "Default")
      (node (ref "ADC") (pin "16") (pinfunction "CH8_16") (pintype "bidirectional"))
      (node (ref "C18") (pin "1") (pinfunction "1_1") (pintype "passive"))
      (node (ref "C19") (pin "2") (pinfunction "2_2") (pintype "passive"))
      (node (ref "R21") (pin "1") (pinfunction "1_1") (pintype "passive"))
    )
    (net (code "21") (name "Net-(ADC-CH9)") (class "Default")
      (node (ref "ADC") (pin "17") (pinfunction "CH9_17") (pintype "bidirectional"))
      (node (ref "C18") (pin "2") (pinfunction "2_2") (pintype "passive"))
      (node (ref "C20") (pin "1") (pinfunction "1_1") (pintype "passive"))
      (node (ref "R22") (pin "1") (pinfunction "1_1") (pintype "passive"))
    )
    (net (code "22") (name "Net-(ADC-CH10)") (class "Default")
      (node (ref "ADC") (pin "18") (pinfunction "CH10_18") (pintype "bidirectional"))
      (node (ref "C21") (pin "1") (pinfunction "1_1") (pintype "passive"))
      (node (ref "C22") (pin "2") (pinfunction "2_2") (pintype "passive"))
      (node (ref "R23") (pin "1") (pinfunction "1_1") (pintype "passive"))
    )
    (net (code "23") (name "Net-(ADC-CH11)") (class "Default")
      (node (ref "ADC") (pin "19") (pinfunction "CH11_19") (pintype "bidirectional"))
      (node (ref "C21") (pin "2") (pinfunction "2_2") (pintype "passive"))
      (node (ref "C23") (pin "1") (pinfunction "1_1") (pintype "passive"))
      (node (ref "R24") (pin "1") (pinfunction "1_1") (pintype "passive"))
    )
    (net (code "24") (name "Net-(ADC-CH12)") (class "Default")
      (node (ref "ADC") (pin "20") (pinfunction "CH12_20") (pintype "bidirectional"))
      (node (ref "C24") (pin "1") (pinfunction "1_1") (pintype "passive"))
      (node (ref "C25") (pin "2") (pinfunction "2_2") (pintype "passive"))
      (node (ref "R25") (pin "1") (pinfunction "1_1") (pintype "passive"))
    )
    (net (code "25") (name "Net-(ADC-CH13)") (class "Default")
      (node (ref "ADC") (pin "21") (pinfunction "CH13_21") (pintype "bidirectional"))
      (node (ref "C24") (pin "2") (pinfunction "2_2") (pintype "passive"))
      (node (ref "C26") (pin "1") (pinfunction "1_1") (pintype "passive"))
      (node (ref "R26") (pin "1") (pinfunction "1_1") (pintype "passive"))
    )
    (net (code "26") (name "Net-(ADC-CH14)") (class "Default")
      (node (ref "ADC") (pin "22") (pinfunction "CH14_22") (pintype "bidirectional"))
      (node (ref "C27") (pin "1") (pinfunction "1_1") (pintype "passive"))
      (node (ref "C28") (pin "2") (pinfunction "2_2") (pintype "passive"))
      (node (ref "R27") (pin "1") (pinfunction "1_1") (pintype "passive"))
    )
    (net (code "27") (name "Net-(ADC-CH15)") (class "Default")
      (node (ref "ADC") (pin "23") (pinfunction "CH15_23") (pintype "bidirectional"))
      (node (ref "C27") (pin "2") (pinfunction "2_2") (pintype "passive"))
      (node (ref "C29") (pin "1") (pinfunction "1_1") (pintype "passive"))
      (node (ref "R28") (pin "1") (pinfunction "1_1") (pintype "passive"))
    )
    (net (code "28") (name "Net-(ADC-IN+)") (class "Default")
      (node (ref "ADC") (pin "24") (pinfunction "MUX+_24") (pintype "bidirectional"))
      (node (ref "ADC") (pin "25") (pinfunction "IN+_25") (pintype "bidirectional"))
    )
    (net (code "29") (name "Net-(ADC-IN-)") (class "Default")
      (node (ref "ADC") (pin "26") (pinfunction "IN-_26") (pintype "bidirectional"))
      (node (ref "ADC") (pin "27") (pinfunction "MUX-_27") (pintype "bidirectional"))
    )
    (net (code "30") (name "Net-(ADC-REF+)") (class "Default")
      (node (ref "ADC") (pin "29") (pinfunction "REF+_29") (pintype "bidirectional"))
      (node (ref "C4") (pin "1") (pinfunction "1_1") (pintype "passive"))
      (node (ref "C5") (pin "1") (pinfunction "1_1") (pintype "passive"))
      (node (ref "R1") (pin "1") (pinfunction "1_1") (pintype "passive"))
    )
    (net (code "31") (name "Net-(AMMETER-A0)") (class "Default")
      (node (ref "AMMETER") (pin "2") (pinfunction "A0_2") (pintype "bidirectional"))
      (node (ref "JP11") (pin "2") (pinfunction "2_2") (pintype "passive"))
    )
    (net (code "32") (name "Net-(AMMETER-A1)") (class "Default")
      (node (ref "AMMETER") (pin "1") (pinfunction "A1_1") (pintype "bidirectional"))
      (node (ref "JP8") (pin "2") (pinfunction "2_2") (pintype "passive"))
    )
    (net (code "33") (name "Net-(AMMETER-IN+)") (class "Default")
      (node (ref "AMMETER") (pin "10") (pinfunction "IN+_10") (pintype "bidirectional"))
      (node (ref "C37") (pin "1") (pinfunction "1_1") (pintype "passive"))
      (node (ref "R60") (pin "1") (pinfunction "1_1") (pintype "passive"))
    )
    (net (code "34") (name "Net-(AMMETER-IN-)") (class "Default")
      (node (ref "AMMETER") (pin "9") (pinfunction "IN-_9") (pintype "bidirectional"))
      (node (ref "C37") (pin "2") (pinfunction "2_2") (pintype "passive"))
      (node (ref "R61") (pin "1") (pinfunction "1_1") (pintype "passive"))
    )
    (net (code "35") (name "Net-(C32-Pad1)") (class "Default")
      (node (ref "C32") (pin "1") (pinfunction "1_1") (pintype "passive"))
      (node (ref "R42") (pin "2") (pinfunction "2_2") (pintype "passive"))
      (node (ref "U1") (pin "A5") (pinfunction "A5_A5") (pintype "bidirectional"))
    )
    (net (code "36") (name "Net-(C33-Pad1)") (class "Default")
      (node (ref "C33") (pin "1") (pinfunction "1_1") (pintype "passive"))
      (node (ref "R41") (pin "2") (pinfunction "2_2") (pintype "passive"))
      (node (ref "U1") (pin "A4") (pinfunction "A4_A4") (pintype "bidirectional"))
    )
    (net (code "37") (name "Net-(C34-Pad1)") (class "Default")
      (node (ref "C34") (pin "1") (pinfunction "1_1") (pintype "passive"))
      (node (ref "R40") (pin "2") (pinfunction "2_2") (pintype "passive"))
      (node (ref "U1") (pin "A3") (pinfunction "A3_A3") (pintype "bidirectional"))
    )
    (net (code "38") (name "Net-(C35-Pad1)") (class "Default")
      (node (ref "C35") (pin "1") (pinfunction "1_1") (pintype "passive"))
      (node (ref "R39") (pin "2") (pinfunction "2_2") (pintype "passive"))
      (node (ref "U1") (pin "A2") (pinfunction "A2_A2") (pintype "bidirectional"))
    )
    (net (code "39") (name "Net-(C40-Pad2)") (class "Default")
      (node (ref "C40") (pin "2") (pinfunction "2_2") (pintype "passive"))
      (node (ref "JP-GP2") (pin "14") (pinfunction "14_14") (pintype "passive"))
    )
    (net (code "40") (name "Net-(C41-Pad2)") (class "Default")
      (node (ref "C41") (pin "2") (pinfunction "2_2") (pintype "passive"))
      (node (ref "JP-GP2") (pin "16") (pinfunction "16_16") (pintype "passive"))
    )
    (net (code "41") (name "Net-(C43-Pad1)") (class "Default")
      (node (ref "C43") (pin "1") (pinfunction "1_1") (pintype "passive"))
      (node (ref "R38") (pin "2") (pinfunction "2_2") (pintype "passive"))
      (node (ref "U1") (pin "A1") (pinfunction "A1_A1") (pintype "bidirectional"))
    )
    (net (code "42") (name "Net-(C43-Pad2)") (class "Default")
      (node (ref "C43") (pin "2") (pinfunction "2_2") (pintype "passive"))
      (node (ref "JP-GP1") (pin "14") (pinfunction "14_14") (pintype "passive"))
    )
    (net (code "43") (name "Net-(C44-Pad1)") (class "Default")
      (node (ref "C44") (pin "1") (pinfunction "1_1") (pintype "passive"))
      (node (ref "R37") (pin "2") (pinfunction "2_2") (pintype "passive"))
      (node (ref "U1") (pin "A0") (pinfunction "A0_A0") (pintype "bidirectional"))
    )
    (net (code "44") (name "Net-(C44-Pad2)") (class "Default")
      (node (ref "C44") (pin "2") (pinfunction "2_2") (pintype "passive"))
      (node (ref "JP-GP1") (pin "16") (pinfunction "16_16") (pintype "passive"))
    )
    (net (code "45") (name "Net-(C48-Pad1)") (class "Default")
      (node (ref "C48") (pin "1") (pinfunction "1_1") (pintype "passive"))
      (node (ref "J-TACH") (pin "1") (pinfunction "1_1") (pintype "passive"))
      (node (ref "JP-TACH") (pin "1") (pinfunction "1_1") (pintype "passive"))
    )
    (net (code "46") (name "Net-(C48-Pad2)") (class "Default")
      (node (ref "C48") (pin "2") (pinfunction "2_2") (pintype "passive"))
      (node (ref "JP-TACH") (pin "2") (pinfunction "2_2") (pintype "passive"))
      (node (ref "R70") (pin "1") (pinfunction "1_1") (pintype "passive"))
    )
    (net (code "47") (name "Net-(C49-Pad1)") (class "Default")
      (node (ref "C49") (pin "1") (pinfunction "1_1") (pintype "passive"))
      (node (ref "J-TACH") (pin "2") (pinfunction "2_2") (pintype "passive"))
      (node (ref "JP-TACH") (pin "3") (pinfunction "3_3") (pintype "passive"))
    )
    (net (code "48") (name "Net-(C49-Pad2)") (class "Default")
      (node (ref "C49") (pin "2") (pinfunction "2_2") (pintype "passive"))
      (node (ref "JP-TACH") (pin "4") (pinfunction "4_4") (pintype "passive"))
      (node (ref "R71") (pin "1") (pinfunction "1_1") (pintype "passive"))
    )
    (net (code "49") (name "Net-(D1-PadA)") (class "Default")
      (node (ref "D1") (pin "A") (pinfunction "A_A") (pintype "passive"))
      (node (ref "D2") (pin "A") (pinfunction "A_A") (pintype "passive"))
      (node (ref "D6") (pin "C") (pinfunction "C_C") (pintype "passive"))
      (node (ref "R70") (pin "2") (pinfunction "2_2") (pintype "passive"))
      (node (ref "R72") (pin "2") (pinfunction "2_2") (pintype "passive"))
    )
    (net (code "50") (name "Net-(D2-PadC)") (class "Default")
      (node (ref "D2") (pin "C") (pinfunction "C_C") (pintype "passive"))
      (node (ref "R74") (pin "1") (pinfunction "1_1") (pintype "passive"))
    )
    (net (code "51") (name "Net-(D3-PadA)") (class "Default")
      (node (ref "D3") (pin "A") (pinfunction "A_A") (pintype "passive"))
      (node (ref "D4") (pin "A") (pinfunction "A_A") (pintype "passive"))
      (node (ref "D5") (pin "C") (pinfunction "C_C") (pintype "passive"))
      (node (ref "R71") (pin "2") (pinfunction "2_2") (pintype "passive"))
      (node (ref "R73") (pin "2") (pinfunction "2_2") (pintype "passive"))
    )
    (net (code "52") (name "Net-(D3-PadC)") (class "Default")
      (node (ref "D3") (pin "C") (pinfunction "C_C") (pintype "passive"))
      (node (ref "R75") (pin "1") (pinfunction "1_1") (pintype "passive"))
    )
    (net (code "53") (name "Net-(IC1-CONT1)") (class "Default")
      (node (ref "C46") (pin "1") (pinfunction "1_1") (pintype "passive"))
      (node (ref "IC1") (pin "3") (pinfunction "CONT1_3") (pintype "input"))
    )
    (net (code "54") (name "Net-(IC1-CONT2)") (class "Default")
      (node (ref "C45") (pin "1") (pinfunction "1_1") (pintype "passive"))
      (node (ref "IC1") (pin "11") (pinfunction "CONT2_11") (pintype "input"))
    )
    (net (code "55") (name "Net-(IC1-OUT1)") (class "Default")
      (node (ref "IC1") (pin "5") (pinfunction "OUT1_5") (pintype "output"))
      (node (ref "JP13") (pin "2") (pinfunction "2_2") (pintype "passive"))
    )
    (net (code "56") (name "Net-(IC1-OUT2)") (class "Default")
      (node (ref "IC1") (pin "9") (pinfunction "OUT2_9") (pintype "output"))
      (node (ref "JP14") (pin "2") (pinfunction "2_2") (pintype "passive"))
    )
    (net (code "57") (name "Net-(IC1-TRES1)") (class "Default")
      (node (ref "C50") (pin "1") (pinfunction "1_1") (pintype "passive"))
      (node (ref "IC1") (pin "2") (pinfunction "TRES1_2") (pintype "input"))
      (node (ref "IC1") (pin "6") (pinfunction "TRIG1_6") (pintype "input"))
      (node (ref "R74") (pin "2") (pinfunction "2_2") (pintype "passive"))
      (node (ref "R76") (pin "2") (pinfunction "2_2") (pintype "passive"))
    )
    (net (code "58") (name "Net-(IC1-TRES2)") (class "Default")
      (node (ref "C51") (pin "1") (pinfunction "1_1") (pintype "passive"))
      (node (ref "IC1") (pin "12") (pinfunction "TRES2_12") (pintype "input"))
      (node (ref "IC1") (pin "8") (pinfunction "TRIG2_8") (pintype "input"))
      (node (ref "R75") (pin "2") (pinfunction "2_2") (pintype "passive"))
      (node (ref "R77") (pin "2") (pinfunction "2_2") (pintype "passive"))
    )
    (net (code "59") (name "Net-(J-GP0-Pad1)") (class "Default")
      (node (ref "J-GP0") (pin "1") (pinfunction "1_1") (pintype "passive"))
      (node (ref "R37") (pin "1") (pinfunction "1_1") (pintype "passive"))
      (node (ref "R45") (pin "2") (pinfunction "2_2") (pintype "passive"))
    )
    (net (code "60") (name "Net-(J-GP0-Pad2)") (class "Default")
      (node (ref "J-GP0") (pin "2") (pinfunction "2_2") (pintype "passive"))
      (node (ref "R38") (pin "1") (pinfunction "1_1") (pintype "passive"))
      (node (ref "R46") (pin "2") (pinfunction "2_2") (pintype "passive"))
    )
    (net (code "61") (name "Net-(J-GP0-Pad3)") (class "Default")
      (node (ref "J-GP0") (pin "3") (pinfunction "3_3") (pintype "passive"))
      (node (ref "R39") (pin "1") (pinfunction "1_1") (pintype "passive"))
      (node (ref "R47") (pin "2") (pinfunction "2_2") (pintype "passive"))
      (node (ref "R48") (pin "2") (pinfunction "2_2") (pintype "passive"))
    )
    (net (code "62") (name "Net-(J-GP0-Pad4)") (class "Default")
      (node (ref "J-GP0") (pin "4") (pinfunction "4_4") (pintype "passive"))
      (node (ref "R40") (pin "1") (pinfunction "1_1") (pintype "passive"))
      (node (ref "R49") (pin "2") (pinfunction "2_2") (pintype "passive"))
      (node (ref "R50") (pin "2") (pinfunction "2_2") (pintype "passive"))
    )
    (net (code "63") (name "Net-(J-GP0-Pad5)") (class "Default")
      (node (ref "J-GP0") (pin "5") (pinfunction "5_5") (pintype "passive"))
      (node (ref "R41") (pin "1") (pinfunction "1_1") (pintype "passive"))
      (node (ref "R51") (pin "2") (pinfunction "2_2") (pintype "passive"))
    )
    (net (code "64") (name "Net-(J-GP0-Pad6)") (class "Default")
      (node (ref "J-GP0") (pin "6") (pinfunction "6_6") (pintype "passive"))
      (node (ref "R42") (pin "1") (pinfunction "1_1") (pintype "passive"))
      (node (ref "R52") (pin "2") (pinfunction "2_2") (pintype "passive"))
    )
    (net (code "65") (name "Net-(J-GP0-Pad7)") (class "Default")
      (node (ref "J-GP0") (pin "7") (pinfunction "7_7") (pintype "passive"))
      (node (ref "R43") (pin "1") (pinfunction "1_1") (pintype "passive"))
      (node (ref "R53") (pin "2") (pinfunction "2_2") (pintype "passive"))
      (node (ref "R54") (pin "2") (pinfunction "2_2") (pintype "passive"))
    )
    (net (code "66") (name "Net-(J-GP0-Pad8)") (class "Default")
      (node (ref "J-GP0") (pin "8") (pinfunction "8_8") (pintype "passive"))
      (node (ref "R44") (pin "1") (pinfunction "1_1") (pintype "passive"))
      (node (ref "R55") (pin "2") (pinfunction "2_2") (pintype "passive"))
      (node (ref "R56") (pin "2") (pinfunction "2_2") (pintype "passive"))
    )
    (net (code "67") (name "Net-(J-GP1-Pad1)") (class "Default")
      (node (ref "J-GP1") (pin "1") (pinfunction "1_1") (pintype "passive"))
      (node (ref "R62") (pin "2") (pinfunction "2_2") (pintype "passive"))
      (node (ref "R63") (pin "2") (pinfunction "2_2") (pintype "passive"))
      (node (ref "R64") (pin "2") (pinfunction "2_2") (pintype "passive"))
      (node (ref "R68") (pin "2") (pinfunction "2_2") (pintype "passive"))
    )
    (net (code "68") (name "Net-(J-GP1-Pad2)") (class "Default")
      (node (ref "J-GP1") (pin "2") (pinfunction "2_2") (pintype "passive"))
      (node (ref "R65") (pin "2") (pinfunction "2_2") (pintype "passive"))
      (node (ref "R66") (pin "2") (pinfunction "2_2") (pintype "passive"))
      (node (ref "R67") (pin "2") (pinfunction "2_2") (pintype "passive"))
      (node (ref "R69") (pin "2") (pinfunction "2_2") (pintype "passive"))
    )
    (net (code "69") (name "Net-(J-GP1-Pad3)") (class "Default")
      (node (ref "J-GP1") (pin "3") (pinfunction "3_3") (pintype "passive"))
      (node (ref "R58") (pin "2") (pinfunction "2_2") (pintype "passive"))
      (node (ref "R59") (pin "1") (pinfunction "1_1") (pintype "passive"))
    )
    (net (code "70") (name "Net-(J-GP1-Pad5)") (class "Default")
      (node (ref "J-GP1") (pin "5") (pinfunction "5_5") (pintype "passive"))
      (node (ref "R60") (pin "2") (pinfunction "2_2") (pintype "passive"))
    )
    (net (code "71") (name "Net-(J-GP1-Pad6)") (class "Default")
      (node (ref "J-GP1") (pin "6") (pinfunction "6_6") (pintype "passive"))
      (node (ref "R61") (pin "2") (pinfunction "2_2") (pintype "passive"))
    )
    (net (code "72") (name "Net-(J-TC0-Pad1)") (class "Default")
      (node (ref "J-TC0") (pin "1") (pinfunction "1_1") (pintype "passive"))
      (node (ref "R5") (pin "1") (pinfunction "1_1") (pintype "passive"))
      (node (ref "R7") (pin "1") (pinfunction "1_1") (pintype "passive"))
    )
    (net (code "73") (name "Net-(J-TC0-Pad2)") (class "Default")
      (node (ref "J-TC0") (pin "2") (pinfunction "2_2") (pintype "passive"))
      (node (ref "R6") (pin "1") (pinfunction "1_1") (pintype "passive"))
      (node (ref "R8") (pin "2") (pinfunction "2_2") (pintype "passive"))
    )
    (net (code "74") (name "Net-(J-TC0-Pad3)") (class "Default")
      (node (ref "J-TC0") (pin "3") (pinfunction "3_3") (pintype "passive"))
      (node (ref "R11") (pin "1") (pinfunction "1_1") (pintype "passive"))
      (node (ref "R9") (pin "1") (pinfunction "1_1") (pintype "passive"))
    )
    (net (code "75") (name "Net-(J-TC0-Pad4)") (class "Default")
      (node (ref "J-TC0") (pin "4") (pinfunction "4_4") (pintype "passive"))
      (node (ref "R10") (pin "1") (pinfunction "1_1") (pintype "passive"))
      (node (ref "R12") (pin "2") (pinfunction "2_2") (pintype "passive"))
    )
    (net (code "76") (name "Net-(J-TC0-Pad5)") (class "Default")
      (node (ref "J-TC0") (pin "5") (pinfunction "5_5") (pintype "passive"))
      (node (ref "R13") (pin "1") (pinfunction "1_1") (pintype "passive"))
      (node (ref "R15") (pin "1") (pinfunction "1_1") (pintype "passive"))
    )
    (net (code "77") (name "Net-(J-TC0-Pad6)") (class "Default")
      (node (ref "J-TC0") (pin "6") (pinfunction "6_6") (pintype "passive"))
      (node (ref "R14") (pin "1") (pinfunction "1_1") (pintype "passive"))
      (node (ref "R16") (pin "2") (pinfunction "2_2") (pintype "passive"))
    )
    (net (code "78") (name "Net-(J-TC0-Pad7)") (class "Default")
      (node (ref "J-TC0") (pin "7") (pinfunction "7_7") (pintype "passive"))
      (node (ref "R17") (pin "1") (pinfunction "1_1") (pintype "passive"))
      (node (ref "R19") (pin "1") (pinfunction "1_1") (pintype "passive"))
    )
    (net (code "79") (name "Net-(J-TC0-Pad8)") (class "Default")
      (node (ref "J-TC0") (pin "8") (pinfunction "8_8") (pintype "passive"))
      (node (ref "R18") (pin "1") (pinfunction "1_1") (pintype "passive"))
      (node (ref "R20") (pin "2") (pinfunction "2_2") (pintype "passive"))
    )
    (net (code "80") (name "Net-(J-TC1-Pad1)") (class "Default")
      (node (ref "J-TC1") (pin "1") (pinfunction "1_1") (pintype "passive"))
      (node (ref "R21") (pin "2") (pinfunction "2_2") (pintype "passive"))
      (node (ref "R29") (pin "1") (pinfunction "1_1") (pintype "passive"))
    )
    (net (code "81") (name "Net-(J-TC1-Pad2)") (class "Default")
      (node (ref "J-TC1") (pin "2") (pinfunction "2_2") (pintype "passive"))
      (node (ref "R22") (pin "2") (pinfunction "2_2") (pintype "passive"))
      (node (ref "R30") (pin "2") (pinfunction "2_2") (pintype "passive"))
    )
    (net (code "82") (name "Net-(J-TC1-Pad3)") (class "Default")
      (node (ref "J-TC1") (pin "3") (pinfunction "3_3") (pintype "passive"))
      (node (ref "R23") (pin "2") (pinfunction "2_2") (pintype "passive"))
      (node (ref "R31") (pin "1") (pinfunction "1_1") (pintype "passive"))
    )
    (net (code "83") (name "Net-(J-TC1-Pad4)") (class "Default")
      (node (ref "J-TC1") (pin "4") (pinfunction "4_4") (pintype "passive"))
      (node (ref "R24") (pin "2") (pinfunction "2_2") (pintype "passive"))
      (node (ref "R32") (pin "2") (pinfunction "2_2") (pintype "passive"))
    )
    (net (code "84") (name "Net-(J-TC1-Pad5)") (class "Default")
      (node (ref "J-TC1") (pin "5") (pinfunction "5_5") (pintype "passive"))
      (node (ref "R25") (pin "2") (pinfunction "2_2") (pintype "passive"))
      (node (ref "R33") (pin "1") (pinfunction "1_1") (pintype "passive"))
    )
    (net (code "85") (name "Net-(J-TC1-Pad6)") (class "Default")
      (node (ref "J-TC1") (pin "6") (pinfunction "6_6") (pintype "passive"))
      (node (ref "R26") (pin "2") (pinfunction "2_2") (pintype "passive"))
      (node (ref "R34") (pin "2") (pinfunction "2_2") (pintype "passive"))
    )
    (net (code "86") (name "Net-(J-TC1-Pad7)") (class "Default")
      (node (ref "J-TC1") (pin "7") (pinfunction "7_7") (pintype "passive"))
      (node (ref "R27") (pin "2") (pinfunction "2_2") (pintype "passive"))
      (node (ref "R35") (pin "1") (pinfunction "1_1") (pintype "passive"))
    )
    (net (code "87") (name "Net-(J-TC1-Pad8)") (class "Default")
      (node (ref "J-TC1") (pin "8") (pinfunction "8_8") (pintype "passive"))
      (node (ref "R28") (pin "2") (pinfunction "2_2") (pintype "passive"))
      (node (ref "R36") (pin "2") (pinfunction "2_2") (pintype "passive"))
    )
    (net (code "88") (name "Net-(JP-GP0-Pad2)") (class "Default")
      (node (ref "JP-GP0") (pin "2") (pinfunction "2_2") (pintype "passive"))
      (node (ref "JP-GP0") (pin "4") (pinfunction "4_4") (pintype "passive"))
      (node (ref "R51") (pin "1") (pinfunction "1_1") (pintype "passive"))
    )
    (net (code "89") (name "Net-(JP-GP0-Pad6)") (class "Default")
      (node (ref "JP-GP0") (pin "6") (pinfunction "6_6") (pintype "passive"))
      (node (ref "JP-GP0") (pin "8") (pinfunction "8_8") (pintype "passive"))
      (node (ref "R52") (pin "1") (pinfunction "1_1") (pintype "passive"))
    )
    (net (code "90") (name "Net-(JP-GP0-Pad10)") (class "Default")
      (node (ref "JP-GP0") (pin "10") (pinfunction "10_10") (pintype "passive"))
      (node (ref "R53") (pin "1") (pinfunction "1_1") (pintype "passive"))
    )
    (net (code "91") (name "Net-(JP-GP0-Pad12)") (class "Default")
      (node (ref "JP-GP0") (pin "12") (pinfunction "12_12") (pintype "passive"))
      (node (ref "R54") (pin "1") (pinfunction "1_1") (pintype "passive"))
    )
    (net (code "92") (name "Net-(JP-GP0-Pad14)") (class "Default")
      (node (ref "JP-GP0") (pin "14") (pinfunction "14_14") (pintype "passive"))
      (node (ref "R55") (pin "1") (pinfunction "1_1") (pintype "passive"))
    )
    (net (code "93") (name "Net-(JP-GP0-Pad16)") (class "Default")
      (node (ref "JP-GP0") (pin "16") (pinfunction "16_16") (pintype "passive"))
      (node (ref "R56") (pin "1") (pinfunction "1_1") (pintype "passive"))
    )
    (net (code "94") (name "Net-(JP-GP1-Pad2)") (class "Default")
      (node (ref "JP-GP1") (pin "2") (pinfunction "2_2") (pintype "passive"))
      (node (ref "R45") (pin "1") (pinfunction "1_1") (pintype "passive"))
    )
    (net (code "95") (name "Net-(JP-GP1-Pad4)") (class "Default")
      (node (ref "JP-GP1") (pin "4") (pinfunction "4_4") (pintype "passive"))
      (node (ref "R46") (pin "1") (pinfunction "1_1") (pintype "passive"))
    )
    (net (code "96") (name "Net-(JP-GP1-Pad6)") (class "Default")
      (node (ref "JP-GP1") (pin "6") (pinfunction "6_6") (pintype "passive"))
      (node (ref "R47") (pin "1") (pinfunction "1_1") (pintype "passive"))
    )
    (net (code "97") (name "Net-(JP-GP1-Pad8)") (class "Default")
      (node (ref "JP-GP1") (pin "8") (pinfunction "8_8") (pintype "passive"))
      (node (ref "R48") (pin "1") (pinfunction "1_1") (pintype "passive"))
    )
    (net (code "98") (name "Net-(JP-GP1-Pad10)") (class "Default")
      (node (ref "JP-GP1") (pin "10") (pinfunction "10_10") (pintype "passive"))
      (node (ref "R49") (pin "1") (pinfunction "1_1") (pintype "passive"))
    )
    (net (code "99") (name "Net-(JP-GP1-Pad12)") (class "Default")
      (node (ref "JP-GP1") (pin "12") (pinfunction "12_12") (pintype "passive"))
      (node (ref "R50") (pin "1") (pinfunction "1_1") (pintype "passive"))
    )
    (net (code "100") (name "Net-(JP-GP2-Pad2)") (class "Default")
      (node (ref "JP-GP2") (pin "2") (pinfunction "2_2") (pintype "passive"))
      (node (ref "R62") (pin "1") (pinfunction "1_1") (pintype "passive"))
    )
    (net (code "101") (name "Net-(JP-GP2-Pad4)") (class "Default")
      (node (ref "JP-GP2") (pin "4") (pinfunction "4_4") (pintype "passive"))
      (node (ref "R63") (pin "1") (pinfunction "1_1") (pintype "passive"))
    )
    (net (code "102") (name "Net-(JP-GP2-Pad6)") (class "Default")
      (node (ref "JP-GP2") (pin "6") (pinfunction "6_6") (pintype "passive"))
      (node (ref "R64") (pin "1") (pinfunction "1_1") (pintype "passive"))
    )
    (net (code "103") (name "Net-(JP-GP2-Pad8)") (class "Default")
      (node (ref "JP-GP2") (pin "8") (pinfunction "8_8") (pintype "passive"))
      (node (ref "R65") (pin "1") (pinfunction "1_1") (pintype "passive"))
    )
    (net (code "104") (name "Net-(JP-GP2-Pad10)") (class "Default")
      (node (ref "JP-GP2") (pin "10") (pinfunction "10_10") (pintype "passive"))
      (node (ref "R66") (pin "1") (pinfunction "1_1") (pintype "passive"))
    )
    (net (code "105") (name "Net-(JP-GP2-Pad12)") (class "Default")
      (node (ref "JP-GP2") (pin "12") (pinfunction "12_12") (pintype "passive"))
      (node (ref "R67") (pin "1") (pinfunction "1_1") (pintype "passive"))
    )
    (net (code "106") (name "Net-(JP9-Pad3)") (class "Default")
      (node (ref "JP9") (pin "3") (pinfunction "3_3") (pintype "passive"))
      (node (ref "U1") (pin "SCL") (pinfunction "SCL_SCL") (pintype "bidirectional"))
    )
    (net (code "107") (name "Net-(JP10-Pad3)") (class "Default")
      (node (ref "JP10") (pin "3") (pinfunction "3_3") (pintype "passive"))
      (node (ref "U1") (pin "SDA") (pinfunction "SDA_SDA") (pintype "bidirectional"))
    )
    (net (code "108") (name "Net-(MAP_SENSOR-VOUT)") (class "Default")
      (node (ref "MAP_SENSOR") (pin "1") (pinfunction "VOUT_1") (pintype "bidirectional"))
      (node (ref "R57") (pin "2") (pinfunction "2_2") (pintype "passive"))
    )
    (net (code "109") (name "Net-(REG_2.5V-OUT)") (class "Default")
      (node (ref "R1") (pin "2") (pinfunction "2_2") (pintype "passive"))
      (node (ref "R2") (pin "2") (pinfunction "2_2") (pintype "passive"))
      (node (ref "REG_2.5V") (pin "1") (pinfunction "OUT_1") (pintype "bidirectional"))
    )
    (net (code "110") (name "S$199") (class "Default")
      (node (ref "C41") (pin "1") (pinfunction "1_1") (pintype "passive"))
      (node (ref "R69") (pin "1") (pinfunction "1_1") (pintype "passive"))
      (node (ref "U1") (pin "D12") (pinfunction "D12_D12") (pintype "bidirectional"))
    )
    (net (code "111") (name "SCL") (class "Default")
      (node (ref "ADC") (pin "2") (pinfunction "SCL_2") (pintype "bidirectional"))
      (node (ref "AMMETER") (pin "5") (pinfunction "SCL_5") (pintype "bidirectional"))
      (node (ref "J-AUXDISP") (pin "P$2") (pinfunction "D-_P$2") (pintype "bidirectional"))
      (node (ref "JP9") (pin "2") (pinfunction "2_2") (pintype "passive"))
      (node (ref "R4") (pin "1") (pinfunction "1_1") (pintype "passive"))
    )
    (net (code "112") (name "SCL{slash}TACH2") (class "Default")
      (node (ref "JP14") (pin "1") (pinfunction "1_1") (pintype "passive"))
      (node (ref "U1") (pin "D3") (pinfunction "D3_D3") (pintype "bidirectional"))
    )
    (net (code "113") (name "SDA") (class "Default")
      (node (ref "ADC") (pin "3") (pinfunction "SDA_3") (pintype "bidirectional"))
      (node (ref "AMMETER") (pin "4") (pinfunction "SDA_4") (pintype "bidirectional"))
      (node (ref "J-AUXDISP") (pin "P$3") (pinfunction "D+_P$3") (pintype "bidirectional"))
      (node (ref "JP10") (pin "2") (pinfunction "2_2") (pintype "passive"))
      (node (ref "R3") (pin "1") (pinfunction "1_1") (pintype "passive"))
    )
    (net (code "114") (name "SDA{slash}TACH1") (class "Default")
      (node (ref "JP13") (pin "1") (pinfunction "1_1") (pintype "passive"))
      (node (ref "U1") (pin "D2") (pinfunction "D2_D2") (pintype "bidirectional"))
    )
    (net (code "115") (name "TACH1") (class "Default")
      (node (ref "JP13") (pin "3") (pinfunction "3_3") (pintype "passive"))
      (node (ref "U1") (pin "D0") (pinfunction "D0_D0") (pintype "bidirectional"))
    )
    (net (code "116") (name "TACH2") (class "Default")
      (node (ref "JP14") (pin "3") (pinfunction "3_3") (pintype "passive"))
      (node (ref "U1") (pin "D1") (pinfunction "D1_D1") (pintype "bidirectional"))
    )
    (net (code "117") (name "VIN") (class "Default")
      (node (ref "AMMETER") (pin "8") (pinfunction "VBUS_8") (pintype "bidirectional"))
      (node (ref "J-GP1") (pin "8") (pinfunction "8_8") (pintype "passive"))
      (node (ref "JP12") (pin "1") (pinfunction "1_1") (pintype "passive"))
      (node (ref "JP12") (pin "2") (pinfunction "2_2") (pintype "passive"))
      (node (ref "U1") (pin "VIN") (pinfunction "VIN_VIN") (pintype "power_in"))
    )
    (net (code "118") (name "unconnected-(AMMETER-NC-Pad3)") (class "Default")
      (node (ref "AMMETER") (pin "3") (pinfunction "NC_3") (pintype "no_connect"))
    )
    (net (code "119") (name "unconnected-(IC1-DIS1-Pad1)") (class "Default")
      (node (ref "IC1") (pin "1") (pinfunction "DIS1_1") (pintype "input"))
    )
    (net (code "120") (name "unconnected-(IC1-DIS2-Pad13)") (class "Default")
      (node (ref "IC1") (pin "13") (pinfunction "DIS2_13") (pintype "input"))
    )
    (net (code "121") (name "unconnected-(J-AUXDISP-ID-PadP$4)") (class "Default")
      (node (ref "J-AUXDISP") (pin "P$4") (pinfunction "ID_P$4") (pintype "bidirectional"))
    )
    (net (code "122") (name "unconnected-(MAP_SENSOR-NC1-Pad4)") (class "Default")
      (node (ref "MAP_SENSOR") (pin "4") (pinfunction "NC1_4") (pintype "no_connect"))
    )
    (net (code "123") (name "unconnected-(MAP_SENSOR-NC2-Pad5)") (class "Default")
      (node (ref "MAP_SENSOR") (pin "5") (pinfunction "NC2_5") (pintype "no_connect"))
    )
    (net (code "124") (name "unconnected-(MAP_SENSOR-NC3-Pad6)") (class "Default")
      (node (ref "MAP_SENSOR") (pin "6") (pinfunction "NC3_6") (pintype "no_connect"))
    )
    (net (code "125") (name "unconnected-(U1-PadAREF)") (class "Default")
      (node (ref "U1") (pin "AREF") (pinfunction "AREF_AREF") (pintype "bidirectional"))
    )
    (net (code "126") (name "unconnected-(U1-PadD10)") (class "Default")
      (node (ref "U1") (pin "D10") (pinfunction "D10_D10") (pintype "bidirectional"))
    )
    (net (code "127") (name "unconnected-(U1-PadD13)") (class "Default")
      (node (ref "U1") (pin "D13") (pinfunction "D13_D13") (pintype "bidirectional"))
    )
    (net (code "128") (name "unconnected-(U1-PadIOREF)") (class "Default")
      (node (ref "U1") (pin "IOREF") (pinfunction "IOREF_IOREF") (pintype "output"))
    )
    (net (code "129") (name "unconnected-(U1-PadRESERVED)") (class "Default")
      (node (ref "U1") (pin "RESERVED") (pinfunction "RESERVED_RESERVED") (pintype "no_connect"))
    )
    (net (code "130") (name "unconnected-(U1-{slash}RESET-PadRESET)") (class "Default")
      (node (ref "U1") (pin "RESET") (pinfunction "/RESET_RESET") (pintype "bidirectional"))
    )
    (net (code "131") (name "{slash}SCL") (class "Default")
      (node (ref "JP9") (pin "1") (pinfunction "1_1") (pintype "passive"))
      (node (ref "U1") (pin "D11") (pinfunction "D11_D11") (pintype "bidirectional"))
    )
    (net (code "132") (name "{slash}SDA") (class "Default")
      (node (ref "JP10") (pin "1") (pinfunction "1_1") (pintype "passive"))
      (node (ref "U1") (pin "D5") (pinfunction "D5_D5") (pintype "bidirectional"))
    )
  )
)
